# circuit.net
KiCad netlist of a schematic drawn in EAGLE
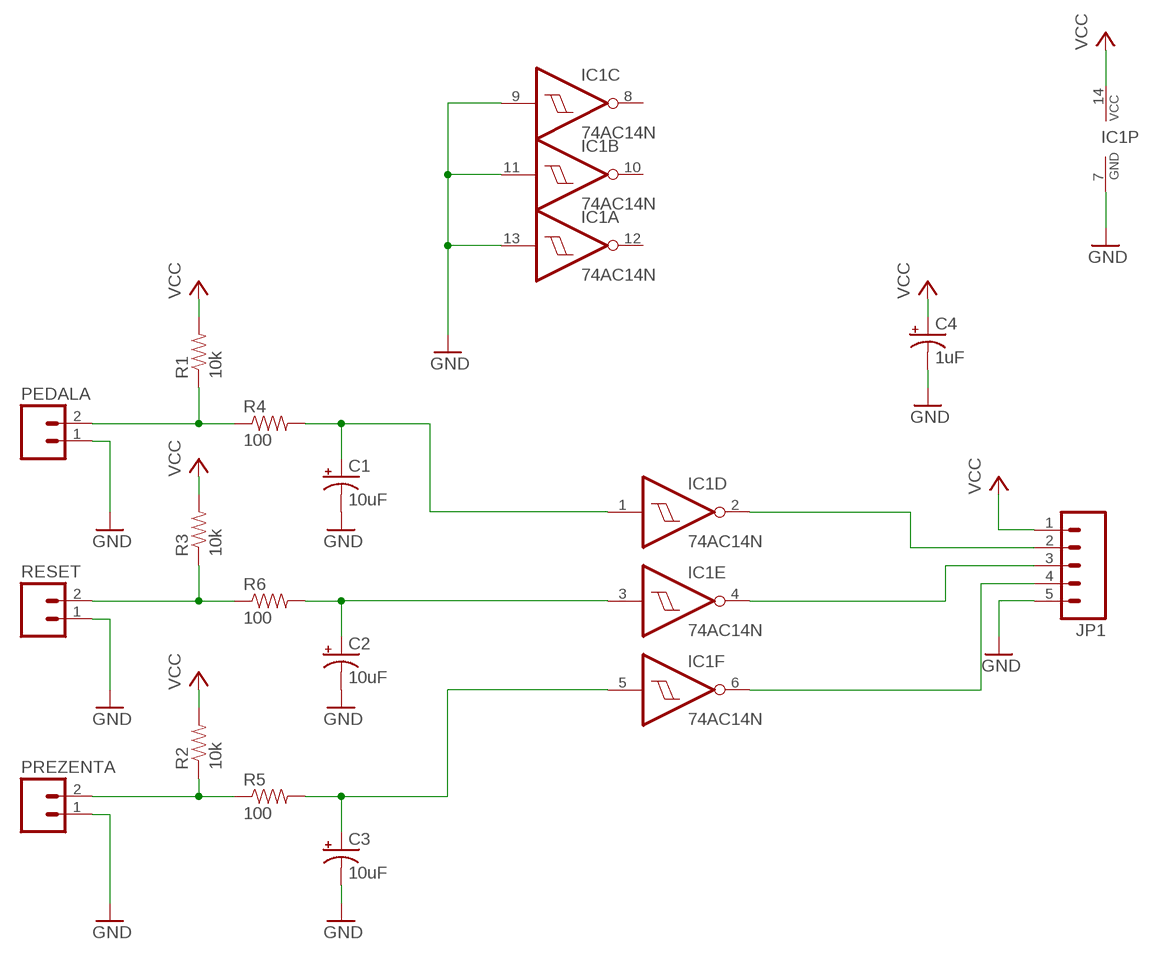
[diagram p0: schematic, sheet 1]

(export (version "E")
  (design (tool "Eeschema 10.0.6"))
  (components
    (comp (ref "C1")
      (value "10uF")
      (footprint "eagle-import:CPOL-RADIAL-10UF-25V")
      (libsource (lib "eagle-import") (part "CAP_POLPTH2"))
    )
    (comp (ref "C2")
      (value "10uF")
      (footprint "eagle-import:CPOL-RADIAL-10UF-25V")
      (libsource (lib "eagle-import") (part "CAP_POLPTH2"))
    )
    (comp (ref "C3")
      (value "10uF")
      (footprint "eagle-import:CPOL-RADIAL-10UF-25V")
      (libsource (lib "eagle-import") (part "CAP_POLPTH2"))
    )
    (comp (ref "C4")
      (value "1uF")
      (footprint "eagle-import:CPOL-RADIAL-10UF-25V")
      (libsource (lib "eagle-import") (part "CAP_POLPTH2"))
    )
    (comp (ref "IC1")
      (value "74AC14N")
      (footprint "eagle-import:DIL14")
      (libsource (lib "eagle-import") (part "7414NAC"))
    )
    (comp (ref "JP1")
      (value "M05PTH_LONGPADS")
      (footprint "eagle-import:1X05_LONGPADS")
      (libsource (lib "eagle-import") (part "M05PTH_LONGPADS"))
    )
    (comp (ref "PEDALA")
      (value "M025MM")
      (footprint "eagle-import:SCREWTERMINAL-5MM-2")
      (libsource (lib "eagle-import") (part "M025MM"))
    )
    (comp (ref "PREZENTA")
      (value "M025MM")
      (footprint "eagle-import:SCREWTERMINAL-5MM-2")
      (libsource (lib "eagle-import") (part "M025MM"))
    )
    (comp (ref "R1")
      (value "10k")
      (footprint "eagle-import:AXIAL-0.4")
      (libsource (lib "eagle-import") (part "RESISTORPTH-1/4W"))
    )
    (comp (ref "R2")
      (value "10k")
      (footprint "eagle-import:AXIAL-0.4")
      (libsource (lib "eagle-import") (part "RESISTORPTH-1/4W"))
    )
    (comp (ref "R3")
      (value "10k")
      (footprint "eagle-import:AXIAL-0.4")
      (libsource (lib "eagle-import") (part "RESISTORPTH-1/4W"))
    )
    (comp (ref "R4")
      (value "100")
      (footprint "eagle-import:AXIAL-0.4")
      (libsource (lib "eagle-import") (part "RESISTORPTH-1/4W"))
    )
    (comp (ref "R5")
      (value "100")
      (footprint "eagle-import:AXIAL-0.4")
      (libsource (lib "eagle-import") (part "RESISTORPTH-1/4W"))
    )
    (comp (ref "R6")
      (value "100")
      (footprint "eagle-import:AXIAL-0.4")
      (libsource (lib "eagle-import") (part "RESISTORPTH-1/4W"))
    )
    (comp (ref "RESET")
      (value "M025MM")
      (footprint "eagle-import:SCREWTERMINAL-5MM-2")
      (libsource (lib "eagle-import") (part "M025MM"))
    )
  )
  (nets
    (net (code "1") (name "GND") (class "Default")
      (node (ref "C1") (pin "2") (pinfunction "-_2") (pintype "passive"))
      (node (ref "C2") (pin "2") (pinfunction "-_2") (pintype "passive"))
      (node (ref "C3") (pin "2") (pinfunction "-_2") (pintype "passive"))
      (node (ref "C4") (pin "2") (pinfunction "-_2") (pintype "passive"))
      (node (ref "IC1") (pin "11") (pinfunction "I_11") (pintype "input"))
      (node (ref "IC1") (pin "13") (pinfunction "I_13") (pintype "input"))
      (node (ref "IC1") (pin "7") (pinfunction "GND_7") (pintype "power_in"))
      (node (ref "IC1") (pin "9") (pinfunction "I_9") (pintype "input"))
      (node (ref "JP1") (pin "5") (pinfunction "5_5") (pintype "passive"))
      (node (ref "PEDALA") (pin "1") (pinfunction "1_1") (pintype "passive"))
      (node (ref "PREZENTA") (pin "1") (pinfunction "1_1") (pintype "passive"))
      (node (ref "RESET") (pin "1") (pinfunction "1_1") (pintype "passive"))
    )
    (net (code "2") (name "Net-(C1-+)") (class "Default")
      (node (ref "C1") (pin "1") (pinfunction "+_1") (pintype "passive"))
      (node (ref "IC1") (pin "1") (pinfunction "I_1") (pintype "input"))
      (node (ref "R4") (pin "P$2") (pinfunction "2_P$2") (pintype "passive"))
    )
    (net (code "3") (name "Net-(C2-+)") (class "Default")
      (node (ref "C2") (pin "1") (pinfunction "+_1") (pintype "passive"))
      (node (ref "IC1") (pin "3") (pinfunction "I_3") (pintype "input"))
      (node (ref "R6") (pin "P$2") (pinfunction "2_P$2") (pintype "passive"))
    )
    (net (code "4") (name "Net-(C3-+)") (class "Default")
      (node (ref "C3") (pin "1") (pinfunction "+_1") (pintype "passive"))
      (node (ref "IC1") (pin "5") (pinfunction "I_5") (pintype "input"))
      (node (ref "R5") (pin "P$2") (pinfunction "2_P$2") (pintype "passive"))
    )
    (net (code "5") (name "Net-(IC1D-O)") (class "Default")
      (node (ref "IC1") (pin "2") (pinfunction "O_2") (pintype "output"))
      (node (ref "JP1") (pin "2") (pinfunction "2_2") (pintype "passive"))
    )
    (net (code "6") (name "Net-(IC1E-O)") (class "Default")
      (node (ref "IC1") (pin "4") (pinfunction "O_4") (pintype "output"))
      (node (ref "JP1") (pin "3") (pinfunction "3_3") (pintype "passive"))
    )
    (net (code "7") (name "Net-(IC1F-O)") (class "Default")
      (node (ref "IC1") (pin "6") (pinfunction "O_6") (pintype "output"))
      (node (ref "JP1") (pin "4") (pinfunction "4_4") (pintype "passive"))
    )
    (net (code "8") (name "Net-(R1-1)") (class "Default")
      (node (ref "PEDALA") (pin "2") (pinfunction "2_2") (pintype "passive"))
      (node (ref "R1") (pin "P$1") (pinfunction "1_P$1") (pintype "passive"))
      (node (ref "R4") (pin "P$1") (pinfunction "1_P$1") (pintype "passive"))
    )
    (net (code "9") (name "Net-(R2-1)") (class "Default")
      (node (ref "PREZENTA") (pin "2") (pinfunction "2_2") (pintype "passive"))
      (node (ref "R2") (pin "P$1") (pinfunction "1_P$1") (pintype "passive"))
      (node (ref "R5") (pin "P$1") (pinfunction "1_P$1") (pintype "passive"))
    )
    (net (code "10") (name "Net-(R3-1)") (class "Default")
      (node (ref "R3") (pin "P$1") (pinfunction "1_P$1") (pintype "passive"))
      (node (ref "R6") (pin "P$1") (pinfunction "1_P$1") (pintype "passive"))
      (node (ref "RESET") (pin "2") (pinfunction "2_2") (pintype "passive"))
    )
    (net (code "11") (name "VCC") (class "Default")
      (node (ref "C4") (pin "1") (pinfunction "+_1") (pintype "passive"))
      (node (ref "IC1") (pin "14") (pinfunction "VCC_14") (pintype "power_in"))
      (node (ref "JP1") (pin "1") (pinfunction "1_1") (pintype "passive"))
      (node (ref "R1") (pin "P$2") (pinfunction "2_P$2") (pintype "passive"))
      (node (ref "R2") (pin "P$2") (pinfunction "2_P$2") (pintype "passive"))
      (node (ref "R3") (pin "P$2") (pinfunction "2_P$2") (pintype "passive"))
    )
    (net (code "12") (name "unconnected-(IC1A-O-Pad12)") (class "Default")
      (node (ref "IC1") (pin "12") (pinfunction "O_12") (pintype "output"))
    )
    (net (code "13") (name "unconnected-(IC1B-O-Pad10)") (class "Default")
      (node (ref "IC1") (pin "10") (pinfunction "O_10") (pintype "output"))
    )
    (net (code "14") (name "unconnected-(IC1C-O-Pad8)") (class "Default")
      (node (ref "IC1") (pin "8") (pinfunction "O_8") (pintype "output"))
    )
  )
)
